# SC.net
KiCad netlist of a schematic drawn in Altium Designer
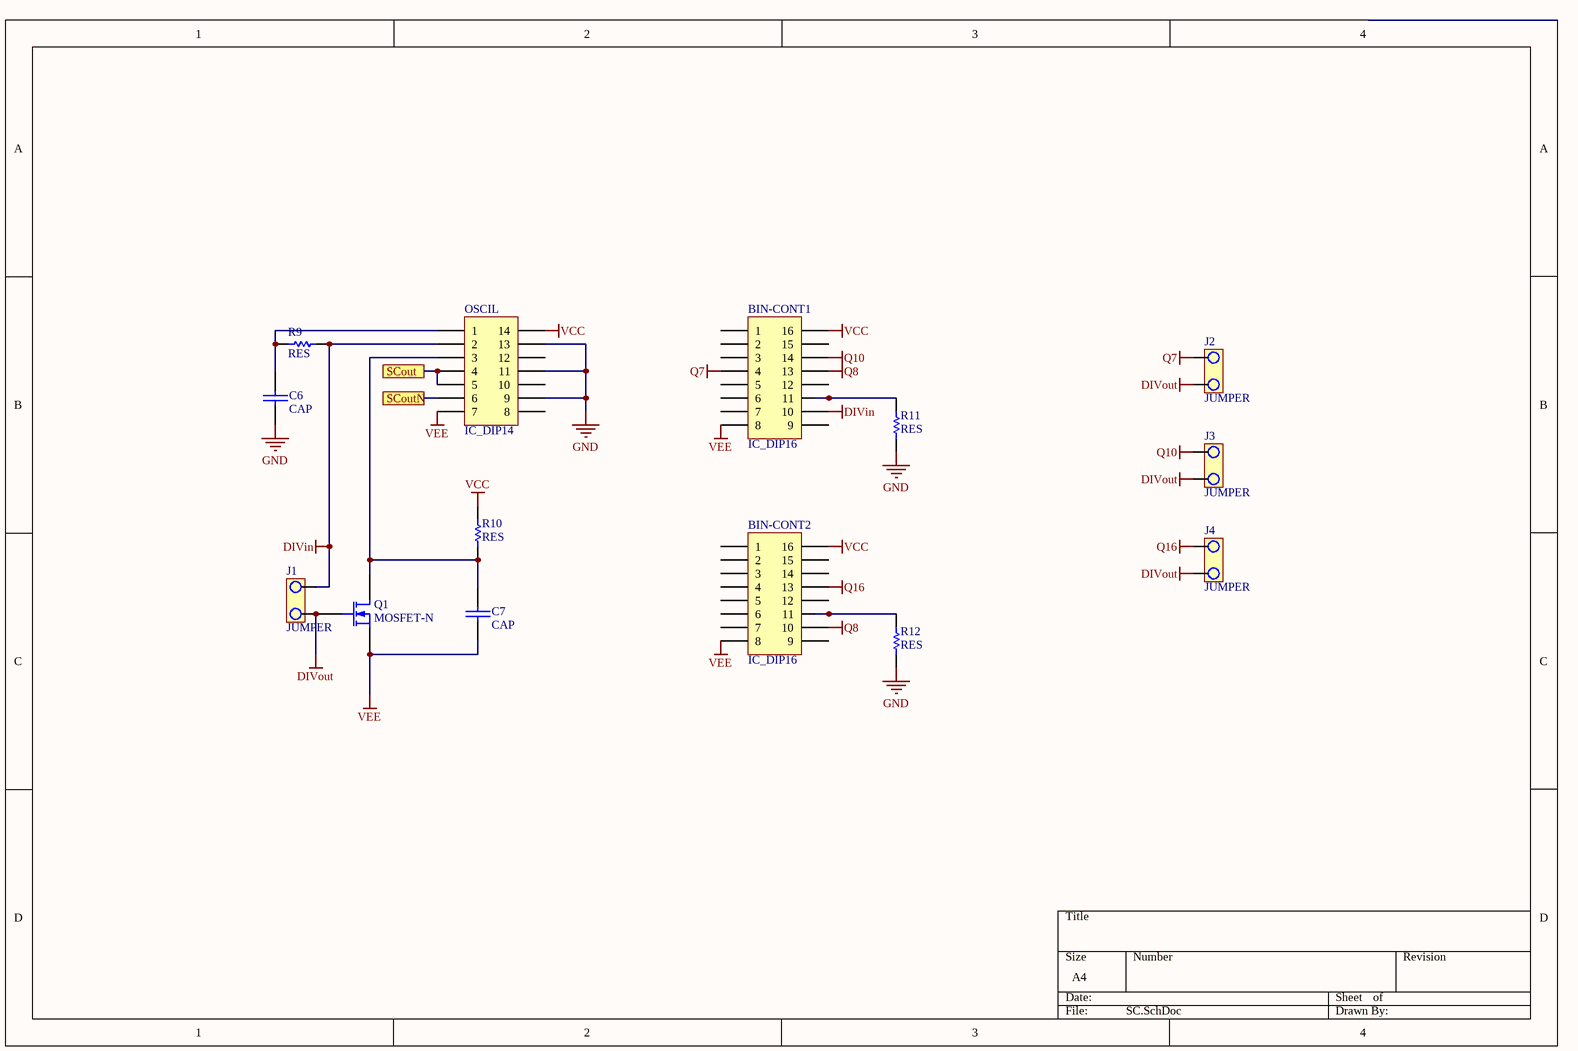
[diagram p0: SC.SchDoc]

(export (version "E")
  (design (tool "Eeschema 10.0.6"))
  (components
    (comp (ref "BIN-CONT1")
      (value "IC_DIP16")
      (footprint "D016_M")
      (libsource (lib "LIBEBAL") (part "IC_DIP16"))
    )
    (comp (ref "BIN-CONT2")
      (value "IC_DIP16")
      (footprint "D016_M")
      (libsource (lib "LIBEBAL") (part "IC_DIP16"))
    )
    (comp (ref "C6") (value "CAP") (footprint "1206") (libsource (lib "LIBEBAL") (part "CAP")))
    (comp (ref "C7") (value "CAP") (footprint "1206") (libsource (lib "LIBEBAL") (part "CAP")))
    (comp (ref "J1") (value "JUMPER") (footprint "0805") (libsource (lib "LIBEBAL") (part "JUMPER")))
    (comp (ref "J2") (value "JUMPER") (footprint "0805") (libsource (lib "") (part "JUMPER_1")))
    (comp (ref "J3") (value "JUMPER") (footprint "0805") (libsource (lib "") (part "JUMPER_1")))
    (comp (ref "J4") (value "JUMPER") (footprint "0805") (libsource (lib "") (part "JUMPER_1")))
    (comp (ref "OSCIL") (value "IC_DIP14") (footprint "D014_M") (libsource (lib "LIBEBAL") (part "IC_DIP14")))
    (comp (ref "Q1")
      (value "MOSFET-N")
      (footprint "SOT-343_M")
      (description "N-Channel MOSFET")
      (fields (field (name "PUBLISHER") "Altium Limited"))
      (libsource (lib "Miscellaneous Devices") (part "MOSFET-N"))
    )
    (comp (ref "R9") (value "RES") (footprint "1206") (libsource (lib "LIBEBAL") (part "RES")))
    (comp (ref "R10") (value "RES") (footprint "1206") (libsource (lib "LIBEBAL") (part "RES")))
    (comp (ref "R11") (value "RES") (footprint "1206") (libsource (lib "LIBEBAL") (part "RES")))
    (comp (ref "R12") (value "RES") (footprint "1206") (libsource (lib "LIBEBAL") (part "RES")))
  )
  (nets
    (net (code "1") (name "/SCout") (class "Default")
      (node (ref "OSCIL") (pin "4") (pinfunction "4_4") (pintype "passive"))
      (node (ref "OSCIL") (pin "5") (pinfunction "5_5") (pintype "passive"))
    )
    (net (code "2") (name "/SCoutN") (class "Default")
      (node (ref "OSCIL") (pin "6") (pinfunction "6_6") (pintype "passive"))
    )
    (net (code "3") (name "DIVin") (class "Default")
      (node (ref "BIN-CONT1") (pin "10") (pinfunction "10_10") (pintype "passive"))
      (node (ref "J1") (pin "1") (pinfunction "1_1") (pintype "passive"))
      (node (ref "OSCIL") (pin "2") (pinfunction "2_2") (pintype "passive"))
      (node (ref "R9") (pin "2") (pinfunction "2_2") (pintype "passive"))
    )
    (net (code "4") (name "DIVout") (class "Default")
      (node (ref "J1") (pin "2") (pinfunction "2_2") (pintype "passive"))
      (node (ref "J2") (pin "1") (pinfunction "1_1") (pintype "passive"))
      (node (ref "J3") (pin "1") (pinfunction "1_1") (pintype "passive"))
      (node (ref "J4") (pin "1") (pinfunction "1_1") (pintype "passive"))
      (node (ref "Q1") (pin "2") (pinfunction "G_2") (pintype "passive"))
    )
    (net (code "5") (name "GND") (class "Default")
      (node (ref "C6") (pin "1") (pinfunction "1_1") (pintype "passive"))
      (node (ref "OSCIL") (pin "11") (pinfunction "11_11") (pintype "passive"))
      (node (ref "OSCIL") (pin "13") (pinfunction "13_13") (pintype "passive"))
      (node (ref "OSCIL") (pin "9") (pinfunction "9_9") (pintype "passive"))
      (node (ref "R11") (pin "1") (pinfunction "1_1") (pintype "passive"))
      (node (ref "R12") (pin "1") (pinfunction "1_1") (pintype "passive"))
    )
    (net (code "6") (name "Net-(BIN-CONT1-Pad11)") (class "Default")
      (node (ref "BIN-CONT1") (pin "11") (pinfunction "11_11") (pintype "passive"))
      (node (ref "R11") (pin "2") (pinfunction "2_2") (pintype "passive"))
    )
    (net (code "7") (name "Net-(BIN-CONT2-Pad11)") (class "Default")
      (node (ref "BIN-CONT2") (pin "11") (pinfunction "11_11") (pintype "passive"))
      (node (ref "R12") (pin "2") (pinfunction "2_2") (pintype "passive"))
    )
    (net (code "8") (name "Net-(C6-Pad2)") (class "Default")
      (node (ref "C6") (pin "2") (pinfunction "2_2") (pintype "passive"))
      (node (ref "OSCIL") (pin "1") (pinfunction "1_1") (pintype "passive"))
      (node (ref "R9") (pin "1") (pinfunction "1_1") (pintype "passive"))
    )
    (net (code "9") (name "Net-(Q1-D)") (class "Default")
      (node (ref "C7") (pin "2") (pinfunction "2_2") (pintype "passive"))
      (node (ref "OSCIL") (pin "3") (pinfunction "3_3") (pintype "passive"))
      (node (ref "Q1") (pin "1") (pinfunction "D_1") (pintype "passive"))
      (node (ref "R10") (pin "1") (pinfunction "1_1") (pintype "passive"))
    )
    (net (code "10") (name "Q7") (class "Default")
      (node (ref "BIN-CONT1") (pin "4") (pinfunction "4_4") (pintype "passive"))
      (node (ref "J2") (pin "2") (pinfunction "2_2") (pintype "passive"))
    )
    (net (code "11") (name "Q8") (class "Default")
      (node (ref "BIN-CONT1") (pin "13") (pinfunction "13_13") (pintype "passive"))
      (node (ref "BIN-CONT2") (pin "10") (pinfunction "10_10") (pintype "passive"))
    )
    (net (code "12") (name "Q10") (class "Default")
      (node (ref "BIN-CONT1") (pin "14") (pinfunction "14_14") (pintype "passive"))
      (node (ref "J3") (pin "2") (pinfunction "2_2") (pintype "passive"))
    )
    (net (code "13") (name "Q16") (class "Default")
      (node (ref "BIN-CONT2") (pin "13") (pinfunction "13_13") (pintype "passive"))
      (node (ref "J4") (pin "2") (pinfunction "2_2") (pintype "passive"))
    )
    (net (code "14") (name "VCC") (class "Default")
      (node (ref "BIN-CONT1") (pin "16") (pinfunction "16_16") (pintype "passive"))
      (node (ref "BIN-CONT2") (pin "16") (pinfunction "16_16") (pintype "passive"))
      (node (ref "OSCIL") (pin "14") (pinfunction "14_14") (pintype "passive"))
      (node (ref "R10") (pin "2") (pinfunction "2_2") (pintype "passive"))
    )
    (net (code "15") (name "VEE") (class "Default")
      (node (ref "BIN-CONT1") (pin "8") (pinfunction "8_8") (pintype "passive"))
      (node (ref "BIN-CONT2") (pin "8") (pinfunction "8_8") (pintype "passive"))
      (node (ref "C7") (pin "1") (pinfunction "1_1") (pintype "passive"))
      (node (ref "OSCIL") (pin "7") (pinfunction "7_7") (pintype "passive"))
      (node (ref "Q1") (pin "3") (pinfunction "S_3") (pintype "passive"))
    )
    (net (code "16") (name "unconnected-(BIN-CONT1-Pad1)") (class "Default")
      (node (ref "BIN-CONT1") (pin "1") (pinfunction "1_1") (pintype "passive"))
    )
    (net (code "17") (name "unconnected-(BIN-CONT1-Pad2)") (class "Default")
      (node (ref "BIN-CONT1") (pin "2") (pinfunction "2_2") (pintype "passive"))
    )
    (net (code "18") (name "unconnected-(BIN-CONT1-Pad3)") (class "Default")
      (node (ref "BIN-CONT1") (pin "3") (pinfunction "3_3") (pintype "passive"))
    )
    (net (code "19") (name "unconnected-(BIN-CONT1-Pad5)") (class "Default")
      (node (ref "BIN-CONT1") (pin "5") (pinfunction "5_5") (pintype "passive"))
    )
    (net (code "20") (name "unconnected-(BIN-CONT1-Pad6)") (class "Default")
      (node (ref "BIN-CONT1") (pin "6") (pinfunction "6_6") (pintype "passive"))
    )
    (net (code "21") (name "unconnected-(BIN-CONT1-Pad7)") (class "Default")
      (node (ref "BIN-CONT1") (pin "7") (pinfunction "7_7") (pintype "passive"))
    )
    (net (code "22") (name "unconnected-(BIN-CONT1-Pad9)") (class "Default")
      (node (ref "BIN-CONT1") (pin "9") (pinfunction "9_9") (pintype "passive"))
    )
    (net (code "23") (name "unconnected-(BIN-CONT1-Pad12)") (class "Default")
      (node (ref "BIN-CONT1") (pin "12") (pinfunction "12_12") (pintype "passive"))
    )
    (net (code "24") (name "unconnected-(BIN-CONT1-Pad15)") (class "Default")
      (node (ref "BIN-CONT1") (pin "15") (pinfunction "15_15") (pintype "passive"))
    )
    (net (code "25") (name "unconnected-(BIN-CONT2-Pad1)") (class "Default")
      (node (ref "BIN-CONT2") (pin "1") (pinfunction "1_1") (pintype "passive"))
    )
    (net (code "26") (name "unconnected-(BIN-CONT2-Pad2)") (class "Default")
      (node (ref "BIN-CONT2") (pin "2") (pinfunction "2_2") (pintype "passive"))
    )
    (net (code "27") (name "unconnected-(BIN-CONT2-Pad3)") (class "Default")
      (node (ref "BIN-CONT2") (pin "3") (pinfunction "3_3") (pintype "passive"))
    )
    (net (code "28") (name "unconnected-(BIN-CONT2-Pad4)") (class "Default")
      (node (ref "BIN-CONT2") (pin "4") (pinfunction "4_4") (pintype "passive"))
    )
    (net (code "29") (name "unconnected-(BIN-CONT2-Pad5)") (class "Default")
      (node (ref "BIN-CONT2") (pin "5") (pinfunction "5_5") (pintype "passive"))
    )
    (net (code "30") (name "unconnected-(BIN-CONT2-Pad6)") (class "Default")
      (node (ref "BIN-CONT2") (pin "6") (pinfunction "6_6") (pintype "passive"))
    )
    (net (code "31") (name "unconnected-(BIN-CONT2-Pad7)") (class "Default")
      (node (ref "BIN-CONT2") (pin "7") (pinfunction "7_7") (pintype "passive"))
    )
    (net (code "32") (name "unconnected-(BIN-CONT2-Pad9)") (class "Default")
      (node (ref "BIN-CONT2") (pin "9") (pinfunction "9_9") (pintype "passive"))
    )
    (net (code "33") (name "unconnected-(BIN-CONT2-Pad12)") (class "Default")
      (node (ref "BIN-CONT2") (pin "12") (pinfunction "12_12") (pintype "passive"))
    )
    (net (code "34") (name "unconnected-(BIN-CONT2-Pad14)") (class "Default")
      (node (ref "BIN-CONT2") (pin "14") (pinfunction "14_14") (pintype "passive"))
    )
    (net (code "35") (name "unconnected-(BIN-CONT2-Pad15)") (class "Default")
      (node (ref "BIN-CONT2") (pin "15") (pinfunction "15_15") (pintype "passive"))
    )
    (net (code "36") (name "unconnected-(OSCIL-Pad8)") (class "Default")
      (node (ref "OSCIL") (pin "8") (pinfunction "8_8") (pintype "passive"))
    )
    (net (code "37") (name "unconnected-(OSCIL-Pad10)") (class "Default")
      (node (ref "OSCIL") (pin "10") (pinfunction "10_10") (pintype "passive"))
    )
    (net (code "38") (name "unconnected-(OSCIL-Pad12)") (class "Default")
      (node (ref "OSCIL") (pin "12") (pinfunction "12_12") (pintype "passive"))
    )
  )
)
